# power.net
KiCad netlist of a schematic drawn in Altium Designer
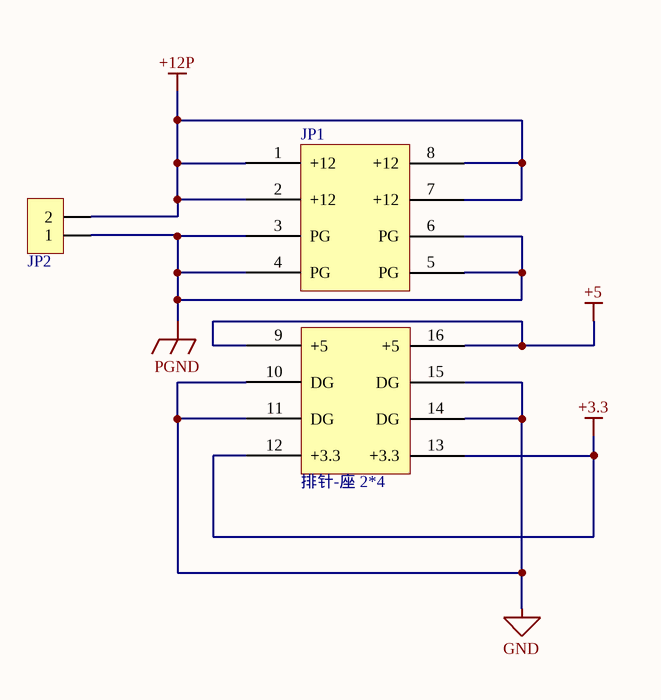
[diagram p0: power.SchDoc]

(export (version "E")
  (design (tool "Eeschema 10.0.6"))
  (components
    (comp (ref "JP1") (value "排针-座 2*4") (footprint "排针-座 2*4") (libsource (lib "Schlib1") (part "排针-座 2*4")))
    (comp (ref "JP2")
      (value "HDR-1X2")
      (footprint "KF128-5.08-2P")
      (description "2P接插件")
      (fields (field (name "版权归属") "源创客"))
      (libsource (lib "4.10 - 接插件-脚距5.08") (part "Header 2"))
    )
  )
  (nets
    (net (code "1") (name "+3.3") (class "Default")
      (node (ref "JP1") (pin "12") (pinfunction "+3.3_12") (pintype "passive"))
      (node (ref "JP1") (pin "13") (pinfunction "+3.3_13") (pintype "passive"))
    )
    (net (code "2") (name "+5") (class "Default")
      (node (ref "JP1") (pin "16") (pinfunction "+5_16") (pintype "passive"))
      (node (ref "JP1") (pin "9") (pinfunction "+5_9") (pintype "passive"))
    )
    (net (code "3") (name "+12P") (class "Default")
      (node (ref "JP1") (pin "1") (pinfunction "+12_1") (pintype "passive"))
      (node (ref "JP1") (pin "2") (pinfunction "+12_2") (pintype "passive"))
      (node (ref "JP1") (pin "7") (pinfunction "+12_7") (pintype "passive"))
      (node (ref "JP1") (pin "8") (pinfunction "+12_8") (pintype "passive"))
      (node (ref "JP2") (pin "2") (pinfunction "2_2") (pintype "passive"))
    )
    (net (code "4") (name "GND") (class "Default")
      (node (ref "JP1") (pin "10") (pinfunction "DG_10") (pintype "passive"))
      (node (ref "JP1") (pin "11") (pinfunction "DG_11") (pintype "passive"))
      (node (ref "JP1") (pin "14") (pinfunction "DG_14") (pintype "passive"))
      (node (ref "JP1") (pin "15") (pinfunction "DG_15") (pintype "passive"))
    )
    (net (code "5") (name "PGND") (class "Default")
      (node (ref "JP1") (pin "3") (pinfunction "PG_3") (pintype "passive"))
      (node (ref "JP1") (pin "4") (pinfunction "PG_4") (pintype "passive"))
      (node (ref "JP1") (pin "5") (pinfunction "PG_5") (pintype "passive"))
      (node (ref "JP1") (pin "6") (pinfunction "PG_6") (pintype "passive"))
      (node (ref "JP2") (pin "1") (pinfunction "1_1") (pintype "passive"))
    )
  )
)
